# main.net
KiCad netlist of a schematic drawn in EAGLE
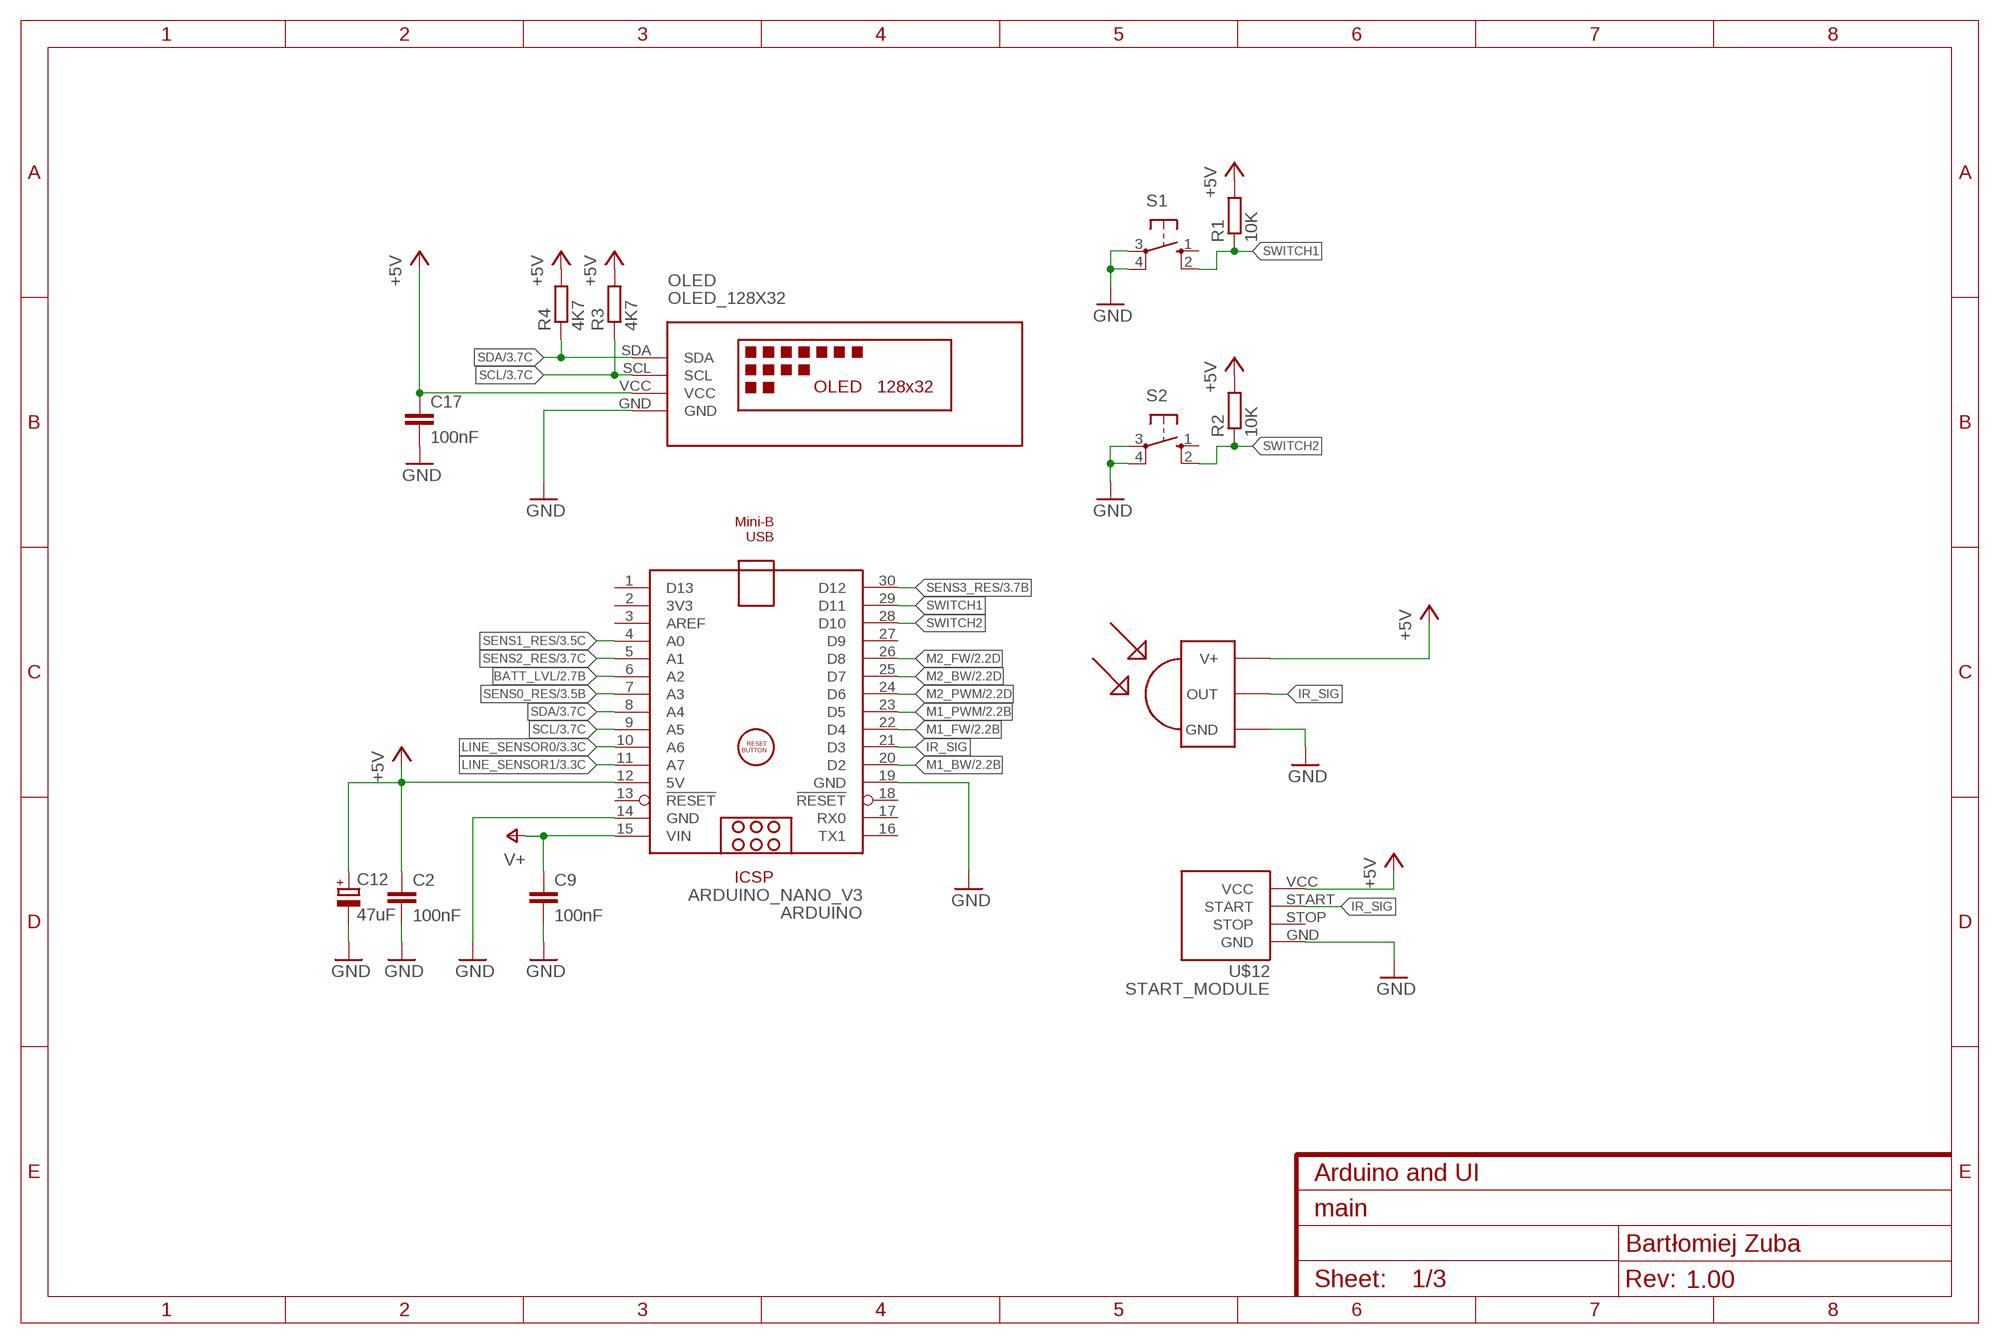
[diagram p0: schematic, sheet 1]
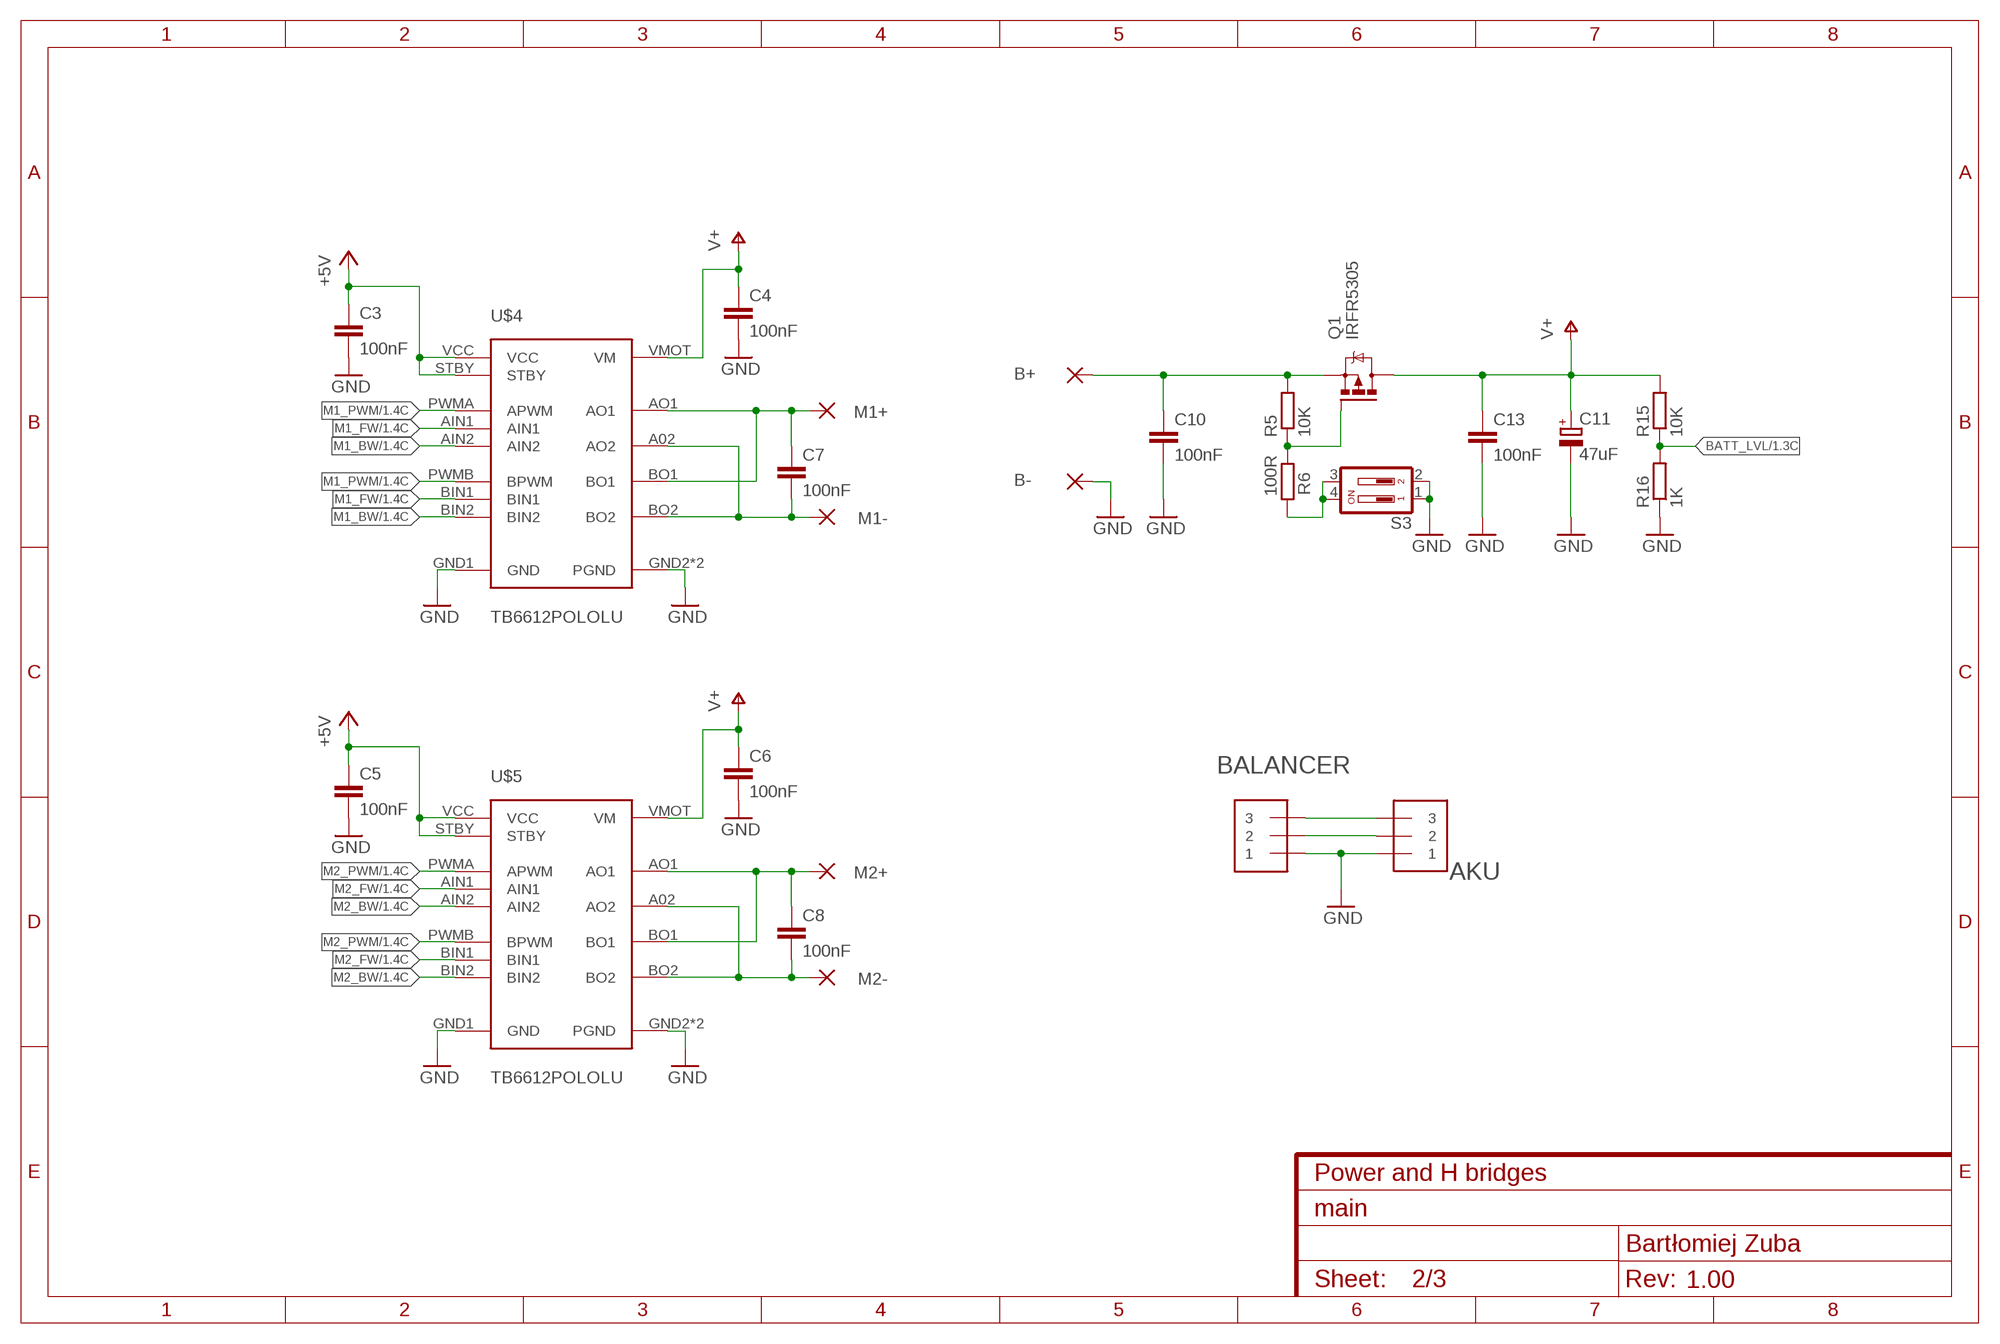
[diagram p1: schematic, sheet 2]
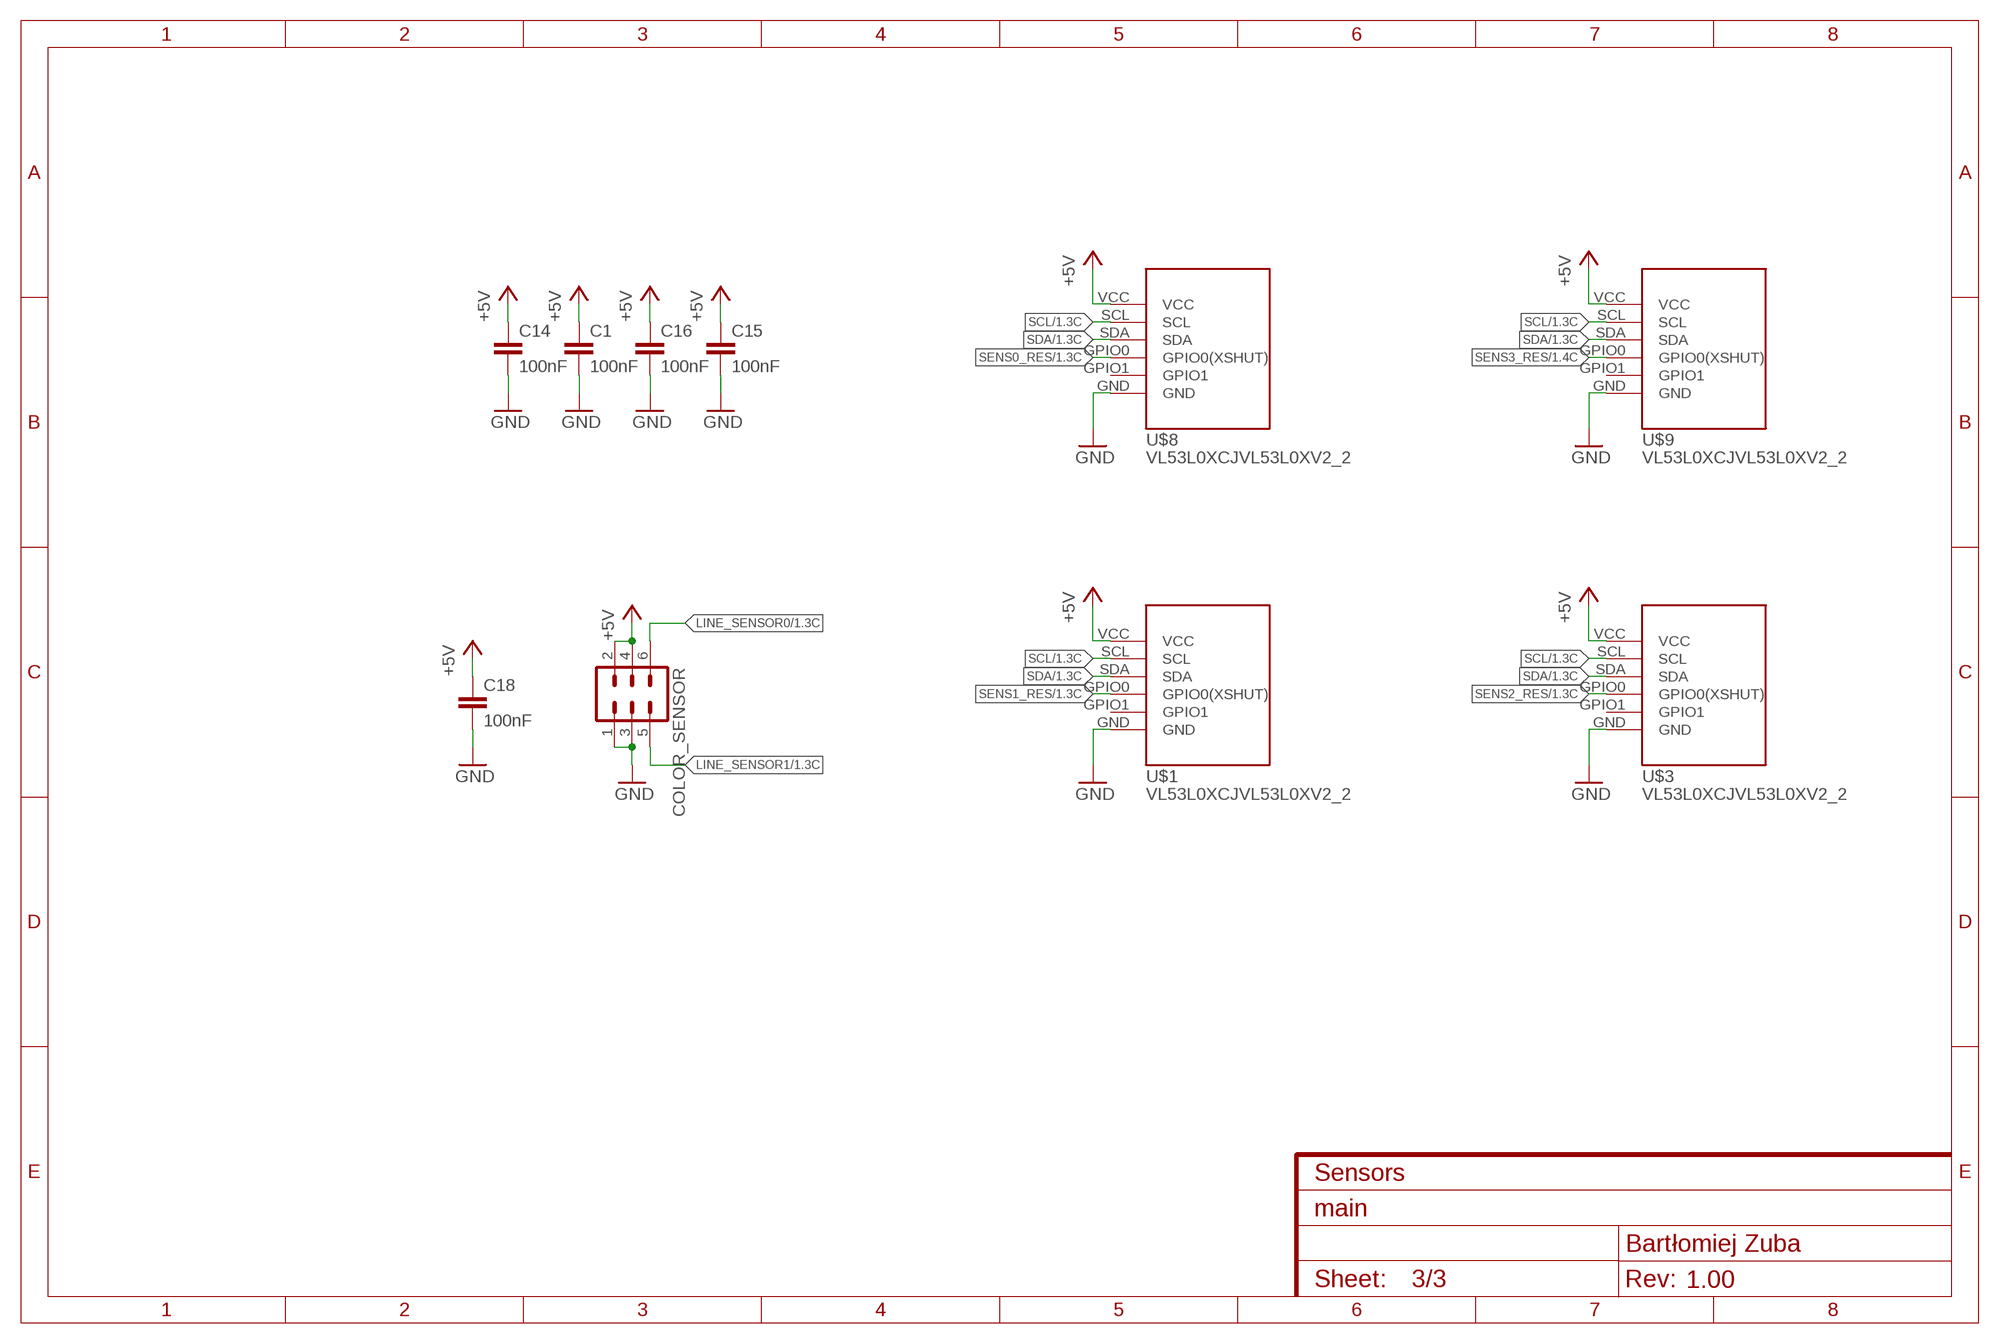
[diagram p2: schematic, sheet 3]

(export (version "E")
  (design (tool "Eeschema 10.0.6"))
  (components
    (comp (ref "ARDUINO")
      (value "ARDUINO_NANO_V3")
      (footprint "eagle-import:ARDUINO_NANO_V3")
      (libsource (lib "eagle-import") (part "ARDUINO_NANO_V3"))
    )
    (comp (ref "C2")
      (value "100nF")
      (footprint "eagle-import:C0805")
      (libsource (lib "eagle-import") (part "C-EUC0805"))
    )
    (comp (ref "C9")
      (value "100nF")
      (footprint "eagle-import:C0805")
      (libsource (lib "eagle-import") (part "C-EUC0805"))
    )
    (comp (ref "C12")
      (value "47uF")
      (footprint "eagle-import:E3,5-8")
      (libsource (lib "eagle-import") (part "CPOL-EUE3.5-8"))
    )
    (comp (ref "C17")
      (value "100nF")
      (footprint "eagle-import:C0805")
      (libsource (lib "eagle-import") (part "C-EUC0805"))
    )
    (comp (ref "OLED")
      (value "OLED_128X32")
      (footprint "eagle-import:OLED")
      (libsource (lib "eagle-import") (part "OLED_128X32"))
    )
    (comp (ref "R1")
      (value "10K")
      (footprint "eagle-import:M0805")
      (libsource (lib "eagle-import") (part "R-EU_M0805"))
    )
    (comp (ref "R2")
      (value "10K")
      (footprint "eagle-import:M0805")
      (libsource (lib "eagle-import") (part "R-EU_M0805"))
    )
    (comp (ref "R3")
      (value "4K7")
      (footprint "eagle-import:M0805")
      (libsource (lib "eagle-import") (part "R-EU_M0805"))
    )
    (comp (ref "R4")
      (value "4K7")
      (footprint "eagle-import:M0805")
      (libsource (lib "eagle-import") (part "R-EU_M0805"))
    )
    (comp (ref "S1")
      (value "10-XX")
      (footprint "eagle-import:B3F-10XX")
      (fields (field (name "MPN") "B3F-1000"))
      (libsource (lib "eagle-import") (part "10-XX"))
    )
    (comp (ref "S2")
      (value "10-XX")
      (footprint "eagle-import:B3F-10XX")
      (fields (field (name "MPN") "B3F-1000"))
      (libsource (lib "eagle-import") (part "10-XX"))
    )
    (comp (ref "U$2")
      (value "TSOP4838")
      (footprint "eagle-import:TSOP")
      (libsource (lib "eagle-import") (part "TSOP4838"))
    )
    (comp (ref "U$12")
      (value "START_MODULE")
      (footprint "eagle-import:START_MODULE")
      (libsource (lib "eagle-import") (part "START_MODULE"))
    )
    (comp (ref "C1")
      (value "100nF")
      (footprint "eagle-import:C0805")
      (libsource (lib "eagle-import") (part "C-EUC0805"))
    )
    (comp (ref "C14")
      (value "100nF")
      (footprint "eagle-import:C0805")
      (libsource (lib "eagle-import") (part "C-EUC0805"))
    )
    (comp (ref "C15")
      (value "100nF")
      (footprint "eagle-import:C0805")
      (libsource (lib "eagle-import") (part "C-EUC0805"))
    )
    (comp (ref "C16")
      (value "100nF")
      (footprint "eagle-import:C0805")
      (libsource (lib "eagle-import") (part "C-EUC0805"))
    )
    (comp (ref "C18")
      (value "100nF")
      (footprint "eagle-import:C0805")
      (libsource (lib "eagle-import") (part "C-EUC0805"))
    )
    (comp (ref "COLOR_SENSOR")
      (value "MA03-2")
      (footprint "eagle-import:MA03-2")
      (libsource (lib "eagle-import") (part "MA03-2"))
    )
    (comp (ref "U$1")
      (value "VL53L0XCJVL53L0XV2_2")
      (footprint "eagle-import:VL53L0X_4")
      (libsource (lib "eagle-import") (part "VL53L0XCJVL53L0XV2_2"))
    )
    (comp (ref "U$3")
      (value "VL53L0XCJVL53L0XV2_2")
      (footprint "eagle-import:VL53L0X_4")
      (libsource (lib "eagle-import") (part "VL53L0XCJVL53L0XV2_2"))
    )
    (comp (ref "U$8")
      (value "VL53L0XCJVL53L0XV2_2")
      (footprint "eagle-import:VL53L0X_4")
      (libsource (lib "eagle-import") (part "VL53L0XCJVL53L0XV2_2"))
    )
    (comp (ref "U$9")
      (value "VL53L0XCJVL53L0XV2_2")
      (footprint "eagle-import:VL53L0X_4")
      (libsource (lib "eagle-import") (part "VL53L0XCJVL53L0XV2_2"))
    )
    (comp (ref "AKU")
      (value "JST_ZH_3")
      (footprint "eagle-import:JST_ZH_3")
      (libsource (lib "eagle-import") (part "JST_ZH_3"))
    )
    (comp (ref "B+")
      (value "2,54/1,0")
      (footprint "eagle-import:2,54_1,0")
      (libsource (lib "eagle-import") (part "2,54/1,0"))
    )
    (comp (ref "B-")
      (value "2,54/1,0")
      (footprint "eagle-import:2,54_1,0")
      (libsource (lib "eagle-import") (part "2,54/1,0"))
    )
    (comp (ref "BALANCER")
      (value "JST_ZH_3")
      (footprint "eagle-import:JST_ZH_3")
      (libsource (lib "eagle-import") (part "JST_ZH_3"))
    )
    (comp (ref "C3")
      (value "100nF")
      (footprint "eagle-import:C0805")
      (libsource (lib "eagle-import") (part "C-EUC0805"))
    )
    (comp (ref "C4")
      (value "100nF")
      (footprint "eagle-import:C0805")
      (libsource (lib "eagle-import") (part "C-EUC0805"))
    )
    (comp (ref "C5")
      (value "100nF")
      (footprint "eagle-import:C0805")
      (libsource (lib "eagle-import") (part "C-EUC0805"))
    )
    (comp (ref "C6")
      (value "100nF")
      (footprint "eagle-import:C0805")
      (libsource (lib "eagle-import") (part "C-EUC0805"))
    )
    (comp (ref "C7")
      (value "100nF")
      (footprint "eagle-import:C0805")
      (libsource (lib "eagle-import") (part "C-EUC0805"))
    )
    (comp (ref "C8")
      (value "100nF")
      (footprint "eagle-import:C0805")
      (libsource (lib "eagle-import") (part "C-EUC0805"))
    )
    (comp (ref "C10")
      (value "100nF")
      (footprint "eagle-import:C0805")
      (libsource (lib "eagle-import") (part "C-EUC0805"))
    )
    (comp (ref "C11")
      (value "47uF")
      (footprint "eagle-import:E3,5-8")
      (libsource (lib "eagle-import") (part "CPOL-EUE3.5-8"))
    )
    (comp (ref "C13")
      (value "100nF")
      (footprint "eagle-import:C0805")
      (libsource (lib "eagle-import") (part "C-EUC0805"))
    )
    (comp (ref "M1+")
      (value "2,54/1,0")
      (footprint "eagle-import:2,54_1,0")
      (libsource (lib "eagle-import") (part "2,54/1,0"))
    )
    (comp (ref "M1-")
      (value "2,54/1,0")
      (footprint "eagle-import:2,54_1,0")
      (libsource (lib "eagle-import") (part "2,54/1,0"))
    )
    (comp (ref "M2+")
      (value "2,54/1,0")
      (footprint "eagle-import:2,54_1,0")
      (libsource (lib "eagle-import") (part "2,54/1,0"))
    )
    (comp (ref "M2-")
      (value "2,54/1,0")
      (footprint "eagle-import:2,54_1,0")
      (libsource (lib "eagle-import") (part "2,54/1,0"))
    )
    (comp (ref "Q1")
      (value "IRFR5305")
      (footprint "eagle-import:D-PAK_TO252AA")
      (libsource (lib "eagle-import") (part "IRF?5305R"))
    )
    (comp (ref "R5")
      (value "10K")
      (footprint "eagle-import:M0805")
      (libsource (lib "eagle-import") (part "R-EU_M0805"))
    )
    (comp (ref "R6")
      (value "100R")
      (footprint "eagle-import:M0805")
      (libsource (lib "eagle-import") (part "R-EU_M0805"))
    )
    (comp (ref "R15")
      (value "10K")
      (footprint "eagle-import:M0805")
      (libsource (lib "eagle-import") (part "R-EU_M0805"))
    )
    (comp (ref "R16")
      (value "1K")
      (footprint "eagle-import:M0805")
      (libsource (lib "eagle-import") (part "R-EU_M0805"))
    )
    (comp (ref "S3")
      (value "DS02")
      (footprint "eagle-import:DS-02")
      (libsource (lib "eagle-import") (part "DS02"))
    )
    (comp (ref "U$4")
      (value "TB6612POLOLU")
      (footprint "eagle-import:POLOLU")
      (libsource (lib "eagle-import") (part "TB6612POLOLU"))
    )
    (comp (ref "U$5")
      (value "TB6612POLOLU")
      (footprint "eagle-import:POLOLU")
      (libsource (lib "eagle-import") (part "TB6612POLOLU"))
    )
  )
  (nets
    (net (code "1") (name "+5V") (class "Default")
      (node (ref "ARDUINO") (pin "12") (pinfunction "5V_12") (pintype "power_in"))
      (node (ref "C1") (pin "1") (pinfunction "1_1") (pintype "passive"))
      (node (ref "C12") (pin "+") (pinfunction "+_+") (pintype "passive"))
      (node (ref "C14") (pin "1") (pinfunction "1_1") (pintype "passive"))
      (node (ref "C15") (pin "1") (pinfunction "1_1") (pintype "passive"))
      (node (ref "C16") (pin "1") (pinfunction "1_1") (pintype "passive"))
      (node (ref "C17") (pin "1") (pinfunction "1_1") (pintype "passive"))
      (node (ref "C18") (pin "1") (pinfunction "1_1") (pintype "passive"))
      (node (ref "C2") (pin "1") (pinfunction "1_1") (pintype "passive"))
      (node (ref "C3") (pin "1") (pinfunction "1_1") (pintype "passive"))
      (node (ref "C5") (pin "1") (pinfunction "1_1") (pintype "passive"))
      (node (ref "COLOR_SENSOR") (pin "2") (pinfunction "2_2") (pintype "passive"))
      (node (ref "COLOR_SENSOR") (pin "4") (pinfunction "4_4") (pintype "passive"))
      (node (ref "OLED") (pin "VCC") (pinfunction "VCC_VCC") (pintype "power_in"))
      (node (ref "R1") (pin "2") (pinfunction "2_2") (pintype "passive"))
      (node (ref "R2") (pin "2") (pinfunction "2_2") (pintype "passive"))
      (node (ref "R3") (pin "2") (pinfunction "2_2") (pintype "passive"))
      (node (ref "R4") (pin "2") (pinfunction "2_2") (pintype "passive"))
      (node (ref "U$1") (pin "VCC") (pinfunction "VCC_VCC") (pintype "bidirectional"))
      (node (ref "U$12") (pin "VCC") (pinfunction "VCC_VCC") (pintype "bidirectional"))
      (node (ref "U$2") (pin "VCC") (pinfunction "V+_VCC") (pintype "bidirectional"))
      (node (ref "U$3") (pin "VCC") (pinfunction "VCC_VCC") (pintype "bidirectional"))
      (node (ref "U$4") (pin "STBY") (pinfunction "STBY_STBY") (pintype "bidirectional"))
      (node (ref "U$4") (pin "VCC") (pinfunction "VCC_VCC") (pintype "bidirectional"))
      (node (ref "U$5") (pin "STBY") (pinfunction "STBY_STBY") (pintype "bidirectional"))
      (node (ref "U$5") (pin "VCC") (pinfunction "VCC_VCC") (pintype "bidirectional"))
      (node (ref "U$8") (pin "VCC") (pinfunction "VCC_VCC") (pintype "bidirectional"))
      (node (ref "U$9") (pin "VCC") (pinfunction "VCC_VCC") (pintype "bidirectional"))
    )
    (net (code "2") (name "BATT_LVL") (class "Default")
      (node (ref "ARDUINO") (pin "6") (pinfunction "A2_6") (pintype "bidirectional"))
      (node (ref "R15") (pin "1") (pinfunction "1_1") (pintype "passive"))
      (node (ref "R16") (pin "2") (pinfunction "2_2") (pintype "passive"))
    )
    (net (code "3") (name "GND") (class "Default")
      (node (ref "AKU") (pin "P$1") (pinfunction "1_P$1") (pintype "bidirectional"))
      (node (ref "ARDUINO") (pin "14") (pinfunction "GND_14") (pintype "power_in"))
      (node (ref "ARDUINO") (pin "19") (pinfunction "GND_19") (pintype "power_in"))
      (node (ref "B-") (pin "1") (pinfunction "P_1") (pintype "passive"))
      (node (ref "BALANCER") (pin "P$1") (pinfunction "1_P$1") (pintype "bidirectional"))
      (node (ref "C1") (pin "2") (pinfunction "2_2") (pintype "passive"))
      (node (ref "C10") (pin "2") (pinfunction "2_2") (pintype "passive"))
      (node (ref "C11") (pin "-") (pinfunction "-_-") (pintype "passive"))
      (node (ref "C12") (pin "-") (pinfunction "-_-") (pintype "passive"))
      (node (ref "C13") (pin "2") (pinfunction "2_2") (pintype "passive"))
      (node (ref "C14") (pin "2") (pinfunction "2_2") (pintype "passive"))
      (node (ref "C15") (pin "2") (pinfunction "2_2") (pintype "passive"))
      (node (ref "C16") (pin "2") (pinfunction "2_2") (pintype "passive"))
      (node (ref "C17") (pin "2") (pinfunction "2_2") (pintype "passive"))
      (node (ref "C18") (pin "2") (pinfunction "2_2") (pintype "passive"))
      (node (ref "C2") (pin "2") (pinfunction "2_2") (pintype "passive"))
      (node (ref "C3") (pin "2") (pinfunction "2_2") (pintype "passive"))
      (node (ref "C4") (pin "2") (pinfunction "2_2") (pintype "passive"))
      (node (ref "C5") (pin "2") (pinfunction "2_2") (pintype "passive"))
      (node (ref "C6") (pin "2") (pinfunction "2_2") (pintype "passive"))
      (node (ref "C9") (pin "2") (pinfunction "2_2") (pintype "passive"))
      (node (ref "COLOR_SENSOR") (pin "1") (pinfunction "1_1") (pintype "passive"))
      (node (ref "COLOR_SENSOR") (pin "3") (pinfunction "3_3") (pintype "passive"))
      (node (ref "OLED") (pin "GND") (pinfunction "GND_GND") (pintype "power_in"))
      (node (ref "R16") (pin "1") (pinfunction "1_1") (pintype "passive"))
      (node (ref "S1") (pin "3") (pinfunction "P_3") (pintype "passive"))
      (node (ref "S1") (pin "4") (pinfunction "P1_4") (pintype "passive"))
      (node (ref "S2") (pin "3") (pinfunction "P_3") (pintype "passive"))
      (node (ref "S2") (pin "4") (pinfunction "P1_4") (pintype "passive"))
      (node (ref "S3") (pin "1") (pinfunction "1_1") (pintype "passive"))
      (node (ref "S3") (pin "2") (pinfunction "2_2") (pintype "passive"))
      (node (ref "U$1") (pin "GND") (pinfunction "GND_GND") (pintype "bidirectional"))
      (node (ref "U$12") (pin "GND") (pinfunction "GND_GND") (pintype "bidirectional"))
      (node (ref "U$2") (pin "GND") (pinfunction "GND_GND") (pintype "bidirectional"))
      (node (ref "U$3") (pin "GND") (pinfunction "GND_GND") (pintype "bidirectional"))
      (node (ref "U$4") (pin "GND1") (pinfunction "GND_GND1") (pintype "bidirectional"))
      (node (ref "U$4") (pin "GND2") (pinfunction "PGND_GND2") (pintype "bidirectional"))
      (node (ref "U$4") (pin "GND3") (pinfunction "PGND_GND3") (pintype "bidirectional"))
      (node (ref "U$5") (pin "GND1") (pinfunction "GND_GND1") (pintype "bidirectional"))
      (node (ref "U$5") (pin "GND2") (pinfunction "PGND_GND2") (pintype "bidirectional"))
      (node (ref "U$5") (pin "GND3") (pinfunction "PGND_GND3") (pintype "bidirectional"))
      (node (ref "U$8") (pin "GND") (pinfunction "GND_GND") (pintype "bidirectional"))
      (node (ref "U$9") (pin "GND") (pinfunction "GND_GND") (pintype "bidirectional"))
    )
    (net (code "4") (name "IR_SIG") (class "Default")
      (node (ref "ARDUINO") (pin "21") (pinfunction "D3_21") (pintype "bidirectional"))
      (node (ref "U$12") (pin "START") (pinfunction "START_START") (pintype "bidirectional"))
      (node (ref "U$2") (pin "OUT") (pinfunction "OUT_OUT") (pintype "bidirectional"))
    )
    (net (code "5") (name "LINE_SENSOR0") (class "Default")
      (node (ref "ARDUINO") (pin "10") (pinfunction "A6_10") (pintype "bidirectional"))
      (node (ref "COLOR_SENSOR") (pin "6") (pinfunction "6_6") (pintype "passive"))
    )
    (net (code "6") (name "LINE_SENSOR1") (class "Default")
      (node (ref "ARDUINO") (pin "11") (pinfunction "A7_11") (pintype "bidirectional"))
      (node (ref "COLOR_SENSOR") (pin "5") (pinfunction "5_5") (pintype "passive"))
    )
    (net (code "7") (name "M1_BW") (class "Default")
      (node (ref "ARDUINO") (pin "20") (pinfunction "D2_20") (pintype "bidirectional"))
      (node (ref "U$4") (pin "AIN2") (pinfunction "AIN2_AIN2") (pintype "bidirectional"))
      (node (ref "U$4") (pin "BIN2") (pinfunction "BIN2_BIN2") (pintype "bidirectional"))
    )
    (net (code "8") (name "M1_FW") (class "Default")
      (node (ref "ARDUINO") (pin "22") (pinfunction "D4_22") (pintype "bidirectional"))
      (node (ref "U$4") (pin "AIN1") (pinfunction "AIN1_AIN1") (pintype "bidirectional"))
      (node (ref "U$4") (pin "BIN1") (pinfunction "BIN1_BIN1") (pintype "bidirectional"))
    )
    (net (code "9") (name "M1_PWM") (class "Default")
      (node (ref "ARDUINO") (pin "23") (pinfunction "D5_23") (pintype "bidirectional"))
      (node (ref "U$4") (pin "PWMA") (pinfunction "APWM_PWMA") (pintype "bidirectional"))
      (node (ref "U$4") (pin "PWMB") (pinfunction "BPWM_PWMB") (pintype "bidirectional"))
    )
    (net (code "10") (name "M2_BW") (class "Default")
      (node (ref "ARDUINO") (pin "25") (pinfunction "D7_25") (pintype "bidirectional"))
      (node (ref "U$5") (pin "AIN2") (pinfunction "AIN2_AIN2") (pintype "bidirectional"))
      (node (ref "U$5") (pin "BIN2") (pinfunction "BIN2_BIN2") (pintype "bidirectional"))
    )
    (net (code "11") (name "M2_FW") (class "Default")
      (node (ref "ARDUINO") (pin "26") (pinfunction "D8_26") (pintype "bidirectional"))
      (node (ref "U$5") (pin "AIN1") (pinfunction "AIN1_AIN1") (pintype "bidirectional"))
      (node (ref "U$5") (pin "BIN1") (pinfunction "BIN1_BIN1") (pintype "bidirectional"))
    )
    (net (code "12") (name "M2_PWM") (class "Default")
      (node (ref "ARDUINO") (pin "24") (pinfunction "D6_24") (pintype "bidirectional"))
      (node (ref "U$5") (pin "PWMA") (pinfunction "APWM_PWMA") (pintype "bidirectional"))
      (node (ref "U$5") (pin "PWMB") (pinfunction "BPWM_PWMB") (pintype "bidirectional"))
    )
    (net (code "13") (name "Net-(AKU-2)") (class "Default")
      (node (ref "AKU") (pin "P$2") (pinfunction "2_P$2") (pintype "bidirectional"))
      (node (ref "BALANCER") (pin "P$2") (pinfunction "2_P$2") (pintype "bidirectional"))
    )
    (net (code "14") (name "Net-(AKU-3)") (class "Default")
      (node (ref "AKU") (pin "P$3") (pinfunction "3_P$3") (pintype "bidirectional"))
      (node (ref "BALANCER") (pin "P$3") (pinfunction "3_P$3") (pintype "bidirectional"))
    )
    (net (code "15") (name "Net-(B+-P)") (class "Default")
      (node (ref "B+") (pin "1") (pinfunction "P_1") (pintype "passive"))
      (node (ref "C10") (pin "1") (pinfunction "1_1") (pintype "passive"))
      (node (ref "Q1") (pin "3") (pinfunction "S_3") (pintype "passive"))
      (node (ref "R5") (pin "2") (pinfunction "2_2") (pintype "passive"))
    )
    (net (code "16") (name "Net-(M1+-P)") (class "Default")
      (node (ref "C7") (pin "1") (pinfunction "1_1") (pintype "passive"))
      (node (ref "M1+") (pin "1") (pinfunction "P_1") (pintype "passive"))
      (node (ref "U$4") (pin "AO1") (pinfunction "AO1_AO1") (pintype "bidirectional"))
      (node (ref "U$4") (pin "BO1") (pinfunction "BO1_BO1") (pintype "bidirectional"))
    )
    (net (code "17") (name "Net-(M1--P)") (class "Default")
      (node (ref "C7") (pin "2") (pinfunction "2_2") (pintype "passive"))
      (node (ref "M1-") (pin "1") (pinfunction "P_1") (pintype "passive"))
      (node (ref "U$4") (pin "A02") (pinfunction "AO2_A02") (pintype "bidirectional"))
      (node (ref "U$4") (pin "BO2") (pinfunction "BO2_BO2") (pintype "bidirectional"))
    )
    (net (code "18") (name "Net-(M2+-P)") (class "Default")
      (node (ref "C8") (pin "1") (pinfunction "1_1") (pintype "passive"))
      (node (ref "M2+") (pin "1") (pinfunction "P_1") (pintype "passive"))
      (node (ref "U$5") (pin "AO1") (pinfunction "AO1_AO1") (pintype "bidirectional"))
      (node (ref "U$5") (pin "BO1") (pinfunction "BO1_BO1") (pintype "bidirectional"))
    )
    (net (code "19") (name "Net-(M2--P)") (class "Default")
      (node (ref "C8") (pin "2") (pinfunction "2_2") (pintype "passive"))
      (node (ref "M2-") (pin "1") (pinfunction "P_1") (pintype "passive"))
      (node (ref "U$5") (pin "A02") (pinfunction "AO2_A02") (pintype "bidirectional"))
      (node (ref "U$5") (pin "BO2") (pinfunction "BO2_BO2") (pintype "bidirectional"))
    )
    (net (code "20") (name "Net-(Q1-G)") (class "Default")
      (node (ref "Q1") (pin "1") (pinfunction "G_1") (pintype "passive"))
      (node (ref "R5") (pin "1") (pinfunction "1_1") (pintype "passive"))
      (node (ref "R6") (pin "1") (pinfunction "1_1") (pintype "passive"))
    )
    (net (code "21") (name "Net-(R6-Pad2)") (class "Default")
      (node (ref "R6") (pin "2") (pinfunction "2_2") (pintype "passive"))
      (node (ref "S3") (pin "3") (pinfunction "3_3") (pintype "passive"))
      (node (ref "S3") (pin "4") (pinfunction "4_4") (pintype "passive"))
    )
    (net (code "22") (name "SCL") (class "Default")
      (node (ref "ARDUINO") (pin "9") (pinfunction "A5_9") (pintype "bidirectional"))
      (node (ref "OLED") (pin "SCL") (pinfunction "SCL_SCL") (pintype "bidirectional"))
      (node (ref "R3") (pin "1") (pinfunction "1_1") (pintype "passive"))
      (node (ref "U$1") (pin "SCL") (pinfunction "SCL_SCL") (pintype "bidirectional"))
      (node (ref "U$3") (pin "SCL") (pinfunction "SCL_SCL") (pintype "bidirectional"))
      (node (ref "U$8") (pin "SCL") (pinfunction "SCL_SCL") (pintype "bidirectional"))
      (node (ref "U$9") (pin "SCL") (pinfunction "SCL_SCL") (pintype "bidirectional"))
    )
    (net (code "23") (name "SDA") (class "Default")
      (node (ref "ARDUINO") (pin "8") (pinfunction "A4_8") (pintype "bidirectional"))
      (node (ref "OLED") (pin "SDA") (pinfunction "SDA_SDA") (pintype "bidirectional"))
      (node (ref "R4") (pin "1") (pinfunction "1_1") (pintype "passive"))
      (node (ref "U$1") (pin "SDA") (pinfunction "SDA_SDA") (pintype "bidirectional"))
      (node (ref "U$3") (pin "SDA") (pinfunction "SDA_SDA") (pintype "bidirectional"))
      (node (ref "U$8") (pin "SDA") (pinfunction "SDA_SDA") (pintype "bidirectional"))
      (node (ref "U$9") (pin "SDA") (pinfunction "SDA_SDA") (pintype "bidirectional"))
    )
    (net (code "24") (name "SENS0_RES") (class "Default")
      (node (ref "ARDUINO") (pin "7") (pinfunction "A3_7") (pintype "bidirectional"))
      (node (ref "U$8") (pin "GPIO0") (pinfunction "GPIO0(XSHUT)_GPIO0") (pintype "bidirectional"))
    )
    (net (code "25") (name "SENS1_RES") (class "Default")
      (node (ref "ARDUINO") (pin "4") (pinfunction "A0_4") (pintype "bidirectional"))
      (node (ref "U$1") (pin "GPIO0") (pinfunction "GPIO0(XSHUT)_GPIO0") (pintype "bidirectional"))
    )
    (net (code "26") (name "SENS2_RES") (class "Default")
      (node (ref "ARDUINO") (pin "5") (pinfunction "A1_5") (pintype "bidirectional"))
      (node (ref "U$3") (pin "GPIO0") (pinfunction "GPIO0(XSHUT)_GPIO0") (pintype "bidirectional"))
    )
    (net (code "27") (name "SENS3_RES") (class "Default")
      (node (ref "ARDUINO") (pin "30") (pinfunction "D12_30") (pintype "bidirectional"))
      (node (ref "U$9") (pin "GPIO0") (pinfunction "GPIO0(XSHUT)_GPIO0") (pintype "bidirectional"))
    )
    (net (code "28") (name "SWITCH1") (class "Default")
      (node (ref "ARDUINO") (pin "29") (pinfunction "D11_29") (pintype "bidirectional"))
      (node (ref "R1") (pin "1") (pinfunction "1_1") (pintype "passive"))
      (node (ref "S1") (pin "2") (pinfunction "S1_2") (pintype "passive"))
    )
    (net (code "29") (name "SWITCH2") (class "Default")
      (node (ref "ARDUINO") (pin "28") (pinfunction "D10_28") (pintype "bidirectional"))
      (node (ref "R2") (pin "1") (pinfunction "1_1") (pintype "passive"))
      (node (ref "S2") (pin "2") (pinfunction "S1_2") (pintype "passive"))
    )
    (net (code "30") (name "V+") (class "Default")
      (node (ref "ARDUINO") (pin "15") (pinfunction "VIN_15") (pintype "power_in"))
      (node (ref "C11") (pin "+") (pinfunction "+_+") (pintype "passive"))
      (node (ref "C13") (pin "1") (pinfunction "1_1") (pintype "passive"))
      (node (ref "C4") (pin "1") (pinfunction "1_1") (pintype "passive"))
      (node (ref "C6") (pin "1") (pinfunction "1_1") (pintype "passive"))
      (node (ref "C9") (pin "1") (pinfunction "1_1") (pintype "passive"))
      (node (ref "Q1") (pin "4") (pinfunction "D_4") (pintype "passive"))
      (node (ref "R15") (pin "2") (pinfunction "2_2") (pintype "passive"))
      (node (ref "U$4") (pin "VMOT") (pinfunction "VM_VMOT") (pintype "bidirectional"))
      (node (ref "U$5") (pin "VMOT") (pinfunction "VM_VMOT") (pintype "bidirectional"))
    )
    (net (code "31") (name "unconnected-(ARDUINO-3V3-Pad2)") (class "Default")
      (node (ref "ARDUINO") (pin "2") (pinfunction "3V3_2") (pintype "output"))
    )
    (net (code "32") (name "unconnected-(ARDUINO-AREF-Pad3)") (class "Default")
      (node (ref "ARDUINO") (pin "3") (pinfunction "AREF_3") (pintype "input"))
    )
    (net (code "33") (name "unconnected-(ARDUINO-D9-Pad27)") (class "Default")
      (node (ref "ARDUINO") (pin "27") (pinfunction "D9_27") (pintype "bidirectional"))
    )
    (net (code "34") (name "unconnected-(ARDUINO-D13-Pad1)") (class "Default")
      (node (ref "ARDUINO") (pin "1") (pinfunction "D13_1") (pintype "bidirectional"))
    )
    (net (code "35") (name "unconnected-(ARDUINO-RX0-Pad17)") (class "Default")
      (node (ref "ARDUINO") (pin "17") (pinfunction "RX0_17") (pintype "bidirectional"))
    )
    (net (code "36") (name "unconnected-(ARDUINO-TX1-Pad16)") (class "Default")
      (node (ref "ARDUINO") (pin "16") (pinfunction "TX1_16") (pintype "bidirectional"))
    )
    (net (code "37") (name "unconnected-(ARDUINO-~{RESET}-Pad13)") (class "Default")
      (node (ref "ARDUINO") (pin "13") (pinfunction "~{RESET}_13") (pintype "input"))
    )
    (net (code "38") (name "unconnected-(ARDUINO-~{RESET}-Pad18)") (class "Default")
      (node (ref "ARDUINO") (pin "18") (pinfunction "~{RESET}_18") (pintype "input"))
    )
    (net (code "39") (name "unconnected-(S1-S-Pad1)") (class "Default")
      (node (ref "S1") (pin "1") (pinfunction "S_1") (pintype "passive"))
    )
    (net (code "40") (name "unconnected-(S2-S-Pad1)") (class "Default")
      (node (ref "S2") (pin "1") (pinfunction "S_1") (pintype "passive"))
    )
    (net (code "41") (name "unconnected-(U$1-PadGPIO1)") (class "Default")
      (node (ref "U$1") (pin "GPIO1") (pinfunction "GPIO1_GPIO1") (pintype "bidirectional"))
    )
    (net (code "42") (name "unconnected-(U$3-PadGPIO1)") (class "Default")
      (node (ref "U$3") (pin "GPIO1") (pinfunction "GPIO1_GPIO1") (pintype "bidirectional"))
    )
    (net (code "43") (name "unconnected-(U$8-PadGPIO1)") (class "Default")
      (node (ref "U$8") (pin "GPIO1") (pinfunction "GPIO1_GPIO1") (pintype "bidirectional"))
    )
    (net (code "44") (name "unconnected-(U$9-PadGPIO1)") (class "Default")
      (node (ref "U$9") (pin "GPIO1") (pinfunction "GPIO1_GPIO1") (pintype "bidirectional"))
    )
    (net (code "45") (name "unconnected-(U$12-PadSTOP)") (class "Default")
      (node (ref "U$12") (pin "STOP") (pinfunction "STOP_STOP") (pintype "bidirectional"))
    )
  )
)
